# FM_Radio_Circuit.net
KiCad netlist of a schematic drawn in EAGLE
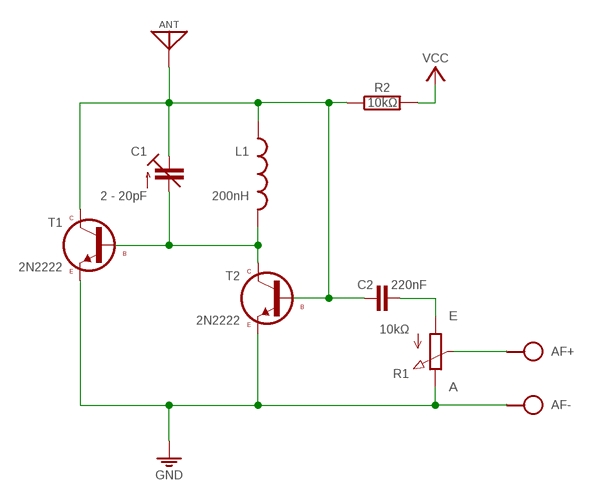
[diagram p0: schematic, sheet 1]

(export (version "E")
  (design (tool "Eeschema 10.0.6"))
  (components
    (comp (ref "AF")
      (value "SPAD+-+-")
      (footprint "eagle-import:SPAD+-")
      (libsource (lib "eagle-import") (part "SPAD+-+-"))
    )
    (comp (ref "ANT")
      (value "ANT")
      (footprint "eagle-import:SPAD")
      (libsource (lib "eagle-import") (part "ANT"))
    )
    (comp (ref "BAT")
      (value "VCC_GNDL")
      (footprint "eagle-import:SPAD-+")
      (libsource (lib "eagle-import") (part "VCC_GNDL"))
    )
    (comp (ref "C1")
      (value "2 - 20pF")
      (footprint "eagle-import:TRIM-2222-808")
      (libsource (lib "eagle-import") (part "C-TR-PH201272222-808-2PINB"))
    )
    (comp (ref "C2")
      (value "220nF")
      (footprint "eagle-import:C050-020X044")
      (libsource (lib "eagle-import") (part "C-H050-020X044"))
    )
    (comp (ref "L1")
      (value "200nH")
      (footprint "eagle-import:L-04_7-V")
      (libsource (lib "eagle-import") (part "L04/7-V"))
    )
    (comp (ref "R1")
      (value "10kΩ")
      (footprint "eagle-import:POT")
      (libsource (lib "eagle-import") (part "POT"))
    )
    (comp (ref "R2")
      (value "10kΩ")
      (footprint "eagle-import:0204_10")
      (libsource (lib "eagle-import") (part "R-H0204/10"))
    )
    (comp (ref "T1")
      (value "2N2222")
      (footprint "eagle-import:TO92-EBC")
      (libsource (lib "eagle-import") (part "2N2222"))
    )
    (comp (ref "T2")
      (value "2N2222")
      (footprint "eagle-import:TO92-EBC")
      (libsource (lib "eagle-import") (part "2N2222"))
    )
  )
  (nets
    (net (code "1") (name "Net-(AFA-P$1)") (class "Default")
      (node (ref "AF") (pin "2") (pinfunction "P$1_2") (pintype "passive"))
      (node (ref "R1") (pin "S") (pinfunction "S_S") (pintype "passive"))
    )
    (net (code "2") (name "Net-(AFB-P$1)") (class "Default")
      (node (ref "AF") (pin "1") (pinfunction "P$1_1") (pintype "passive"))
      (node (ref "BAT") (pin "1") (pinfunction "GND_1") (pintype "power_in"))
      (node (ref "R1") (pin "E") (pinfunction "E_E") (pintype "passive"))
      (node (ref "T1") (pin "E") (pinfunction "E_E") (pintype "passive"))
      (node (ref "T2") (pin "E") (pinfunction "E_E") (pintype "passive"))
    )
    (net (code "3") (name "Net-(BATA-VCC)") (class "Default")
      (node (ref "BAT") (pin "2") (pinfunction "VCC_2") (pintype "power_in"))
      (node (ref "R2") (pin "2") (pinfunction "2_2") (pintype "passive"))
    )
    (net (code "4") (name "Net-(C1-A)") (class "Default")
      (node (ref "C1") (pin "2") (pinfunction "A_2") (pintype "passive"))
      (node (ref "L1") (pin "2") (pinfunction "2_2") (pintype "passive"))
      (node (ref "T1") (pin "B") (pinfunction "B_B") (pintype "passive"))
      (node (ref "T2") (pin "C") (pinfunction "C_C") (pintype "passive"))
    )
    (net (code "5") (name "Net-(C1-E)") (class "Default")
      (node (ref "ANT") (pin "1") (pinfunction "1_1") (pintype "output"))
      (node (ref "C1") (pin "3") (pinfunction "E_3") (pintype "passive"))
      (node (ref "C2") (pin "1") (pinfunction "1_1") (pintype "passive"))
      (node (ref "L1") (pin "1") (pinfunction "1_1") (pintype "passive"))
      (node (ref "R2") (pin "1") (pinfunction "1_1") (pintype "passive"))
      (node (ref "T1") (pin "C") (pinfunction "C_C") (pintype "passive"))
      (node (ref "T2") (pin "B") (pinfunction "B_B") (pintype "passive"))
    )
    (net (code "6") (name "Net-(C2-Pad2)") (class "Default")
      (node (ref "C2") (pin "2") (pinfunction "2_2") (pintype "passive"))
      (node (ref "R1") (pin "A") (pinfunction "A_A") (pintype "passive"))
    )
  )
)
